# CV-module-schematics.net
KiCad netlist of a schematic drawn in EAGLE
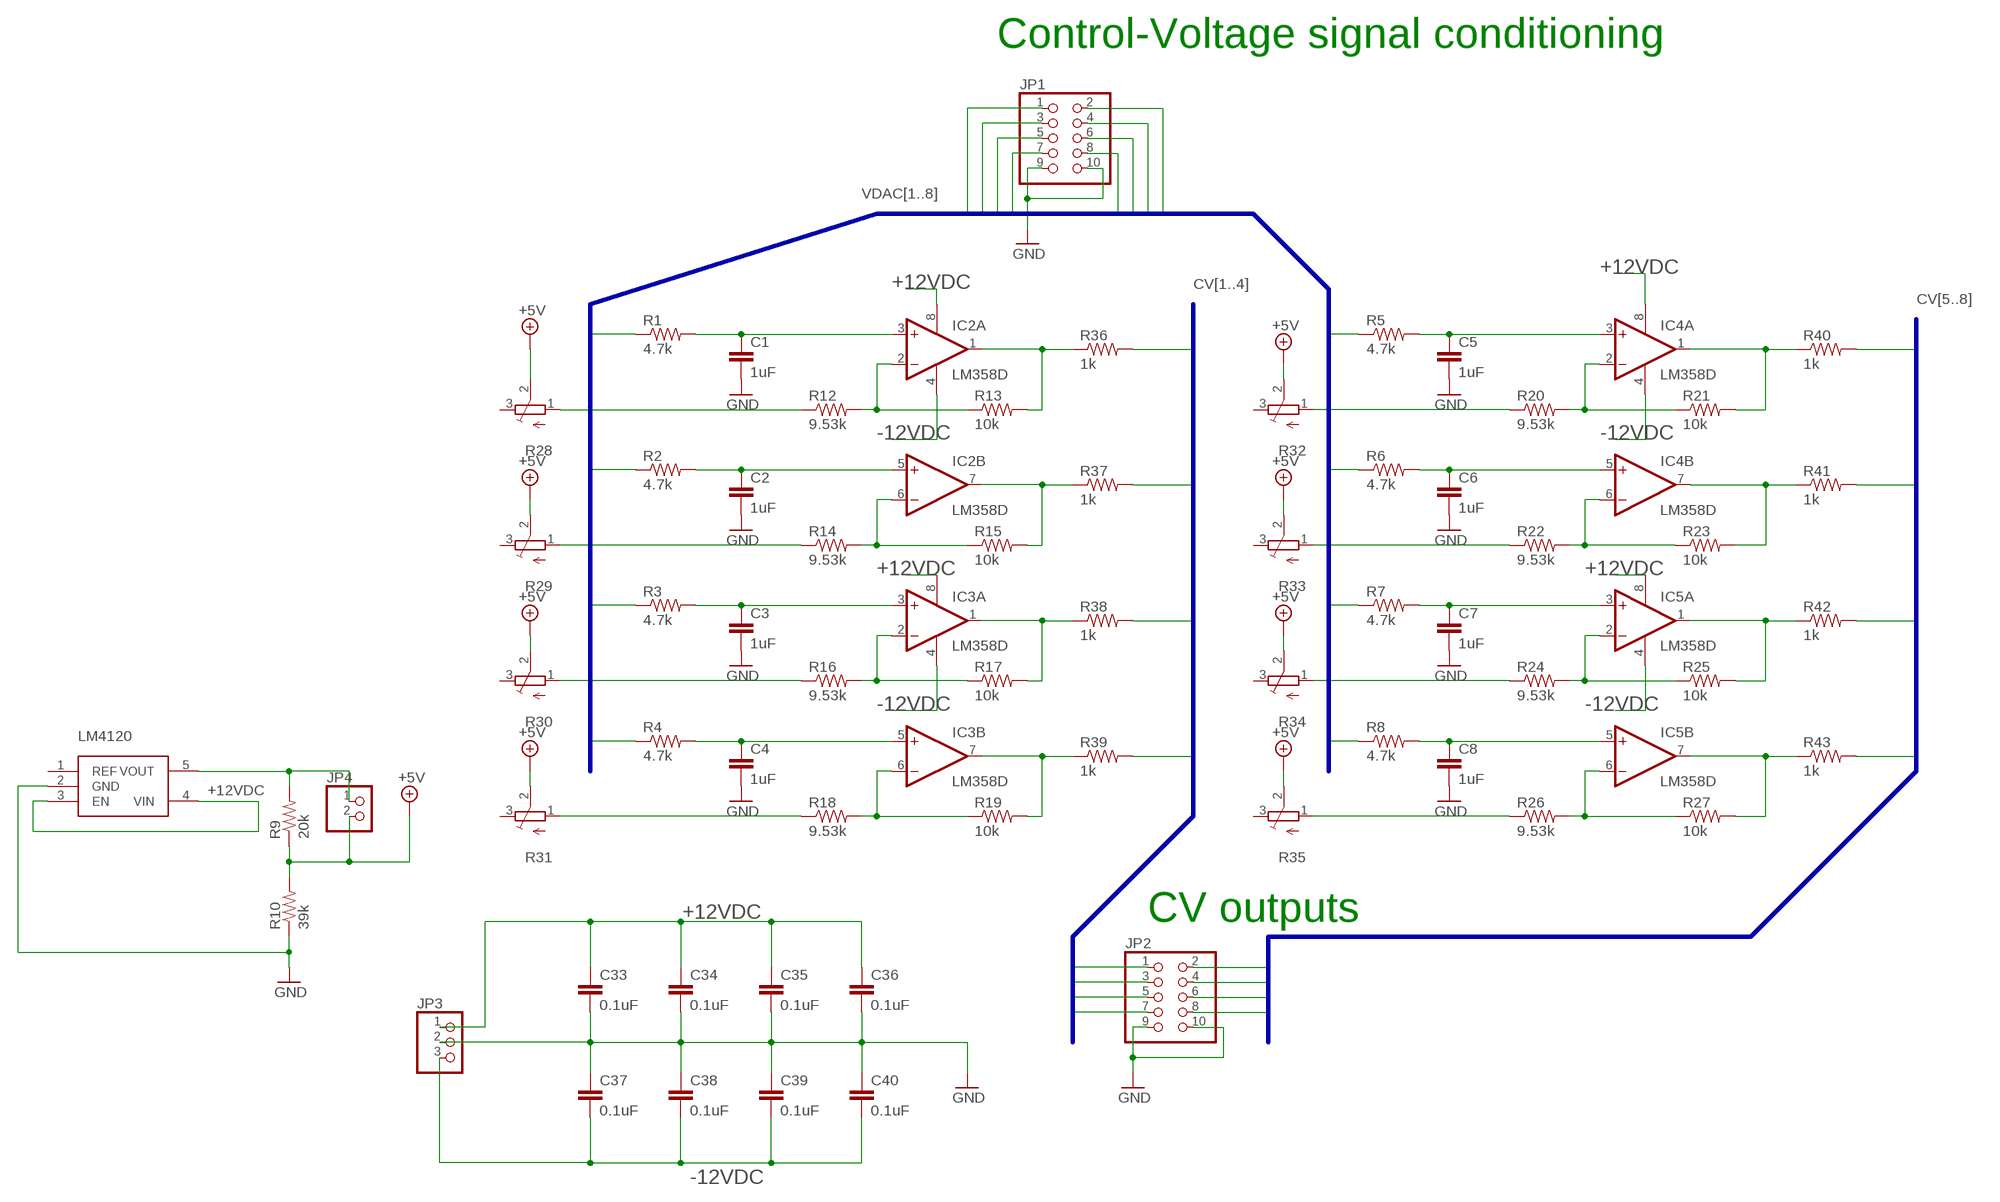
[diagram p0: schematic, sheet 1]

(export (version "E")
  (design (tool "Eeschema 10.0.6"))
  (components
    (comp (ref "C1")
      (value "1uF")
      (footprint "eagle-import:C0603")
      (libsource (lib "eagle-import") (part "C-EUC0603"))
    )
    (comp (ref "C2")
      (value "1uF")
      (footprint "eagle-import:C0603")
      (libsource (lib "eagle-import") (part "C-EUC0603"))
    )
    (comp (ref "C3")
      (value "1uF")
      (footprint "eagle-import:C0603")
      (libsource (lib "eagle-import") (part "C-EUC0603"))
    )
    (comp (ref "C4")
      (value "1uF")
      (footprint "eagle-import:C0603")
      (libsource (lib "eagle-import") (part "C-EUC0603"))
    )
    (comp (ref "C5")
      (value "1uF")
      (footprint "eagle-import:C0603")
      (libsource (lib "eagle-import") (part "C-EUC0603"))
    )
    (comp (ref "C6")
      (value "1uF")
      (footprint "eagle-import:C0603")
      (libsource (lib "eagle-import") (part "C-EUC0603"))
    )
    (comp (ref "C7")
      (value "1uF")
      (footprint "eagle-import:C0603")
      (libsource (lib "eagle-import") (part "C-EUC0603"))
    )
    (comp (ref "C8")
      (value "1uF")
      (footprint "eagle-import:C0603")
      (libsource (lib "eagle-import") (part "C-EUC0603"))
    )
    (comp (ref "C33")
      (value "0.1uF")
      (footprint "eagle-import:C0603")
      (libsource (lib "eagle-import") (part "C-EUC0603"))
    )
    (comp (ref "C34")
      (value "0.1uF")
      (footprint "eagle-import:C0603")
      (libsource (lib "eagle-import") (part "C-EUC0603"))
    )
    (comp (ref "C35")
      (value "0.1uF")
      (footprint "eagle-import:C0603")
      (libsource (lib "eagle-import") (part "C-EUC0603"))
    )
    (comp (ref "C36")
      (value "0.1uF")
      (footprint "eagle-import:C0603")
      (libsource (lib "eagle-import") (part "C-EUC0603"))
    )
    (comp (ref "C37")
      (value "0.1uF")
      (footprint "eagle-import:C0603")
      (libsource (lib "eagle-import") (part "C-EUC0603"))
    )
    (comp (ref "C38")
      (value "0.1uF")
      (footprint "eagle-import:C0603")
      (libsource (lib "eagle-import") (part "C-EUC0603"))
    )
    (comp (ref "C39")
      (value "0.1uF")
      (footprint "eagle-import:C0603")
      (libsource (lib "eagle-import") (part "C-EUC0603"))
    )
    (comp (ref "C40")
      (value "0.1uF")
      (footprint "eagle-import:C0603")
      (libsource (lib "eagle-import") (part "C-EUC0603"))
    )
    (comp (ref "IC2")
      (value "LM358D")
      (footprint "eagle-import:SO08")
      (libsource (lib "eagle-import") (part "LM358D"))
    )
    (comp (ref "IC3")
      (value "LM358D")
      (footprint "eagle-import:SO08")
      (libsource (lib "eagle-import") (part "LM358D"))
    )
    (comp (ref "IC4")
      (value "LM358D")
      (footprint "eagle-import:SO08")
      (libsource (lib "eagle-import") (part "LM358D"))
    )
    (comp (ref "IC5")
      (value "LM358D")
      (footprint "eagle-import:SO08")
      (libsource (lib "eagle-import") (part "LM358D"))
    )
    (comp (ref "JP1")
      (value "PINHD-2X5")
      (footprint "eagle-import:2X05")
      (libsource (lib "eagle-import") (part "PINHD-2X5"))
    )
    (comp (ref "JP2")
      (value "PINHD-2X5")
      (footprint "eagle-import:2X05")
      (libsource (lib "eagle-import") (part "PINHD-2X5"))
    )
    (comp (ref "JP3")
      (value "PINHD-1X3")
      (footprint "eagle-import:1X03")
      (libsource (lib "eagle-import") (part "PINHD-1X3"))
    )
    (comp (ref "JP4")
      (value "PINHD-1X2")
      (footprint "eagle-import:1X02")
      (libsource (lib "eagle-import") (part "PINHD-1X2"))
    )
    (comp (ref "LM4120")
      (value "LM4120")
      (footprint "eagle-import:SOT23-5")
      (libsource (lib "eagle-import") (part "LM4120"))
    )
    (comp (ref "R1")
      (value "4.7k")
      (footprint "eagle-import:R0603")
      (libsource (lib "eagle-import") (part "R-US_R0603"))
    )
    (comp (ref "R2")
      (value "4.7k")
      (footprint "eagle-import:R0603")
      (libsource (lib "eagle-import") (part "R-US_R0603"))
    )
    (comp (ref "R3")
      (value "4.7k")
      (footprint "eagle-import:R0603")
      (libsource (lib "eagle-import") (part "R-US_R0603"))
    )
    (comp (ref "R4")
      (value "4.7k")
      (footprint "eagle-import:R0603")
      (libsource (lib "eagle-import") (part "R-US_R0603"))
    )
    (comp (ref "R5")
      (value "4.7k")
      (footprint "eagle-import:R0603")
      (libsource (lib "eagle-import") (part "R-US_R0603"))
    )
    (comp (ref "R6")
      (value "4.7k")
      (footprint "eagle-import:R0603")
      (libsource (lib "eagle-import") (part "R-US_R0603"))
    )
    (comp (ref "R7")
      (value "4.7k")
      (footprint "eagle-import:R0603")
      (libsource (lib "eagle-import") (part "R-US_R0603"))
    )
    (comp (ref "R8")
      (value "4.7k")
      (footprint "eagle-import:R0603")
      (libsource (lib "eagle-import") (part "R-US_R0603"))
    )
    (comp (ref "R9")
      (value "20k")
      (footprint "eagle-import:R0603")
      (libsource (lib "eagle-import") (part "R-US_R0603"))
    )
    (comp (ref "R10")
      (value "39k")
      (footprint "eagle-import:R0603")
      (libsource (lib "eagle-import") (part "R-US_R0603"))
    )
    (comp (ref "R12")
      (value "9.53k")
      (footprint "eagle-import:R0603")
      (libsource (lib "eagle-import") (part "R-US_R0603"))
    )
    (comp (ref "R13")
      (value "10k")
      (footprint "eagle-import:R0603")
      (libsource (lib "eagle-import") (part "R-US_R0603"))
    )
    (comp (ref "R14")
      (value "9.53k")
      (footprint "eagle-import:R0603")
      (libsource (lib "eagle-import") (part "R-US_R0603"))
    )
    (comp (ref "R15")
      (value "10k")
      (footprint "eagle-import:R0603")
      (libsource (lib "eagle-import") (part "R-US_R0603"))
    )
    (comp (ref "R16")
      (value "9.53k")
      (footprint "eagle-import:R0603")
      (libsource (lib "eagle-import") (part "R-US_R0603"))
    )
    (comp (ref "R17")
      (value "10k")
      (footprint "eagle-import:R0603")
      (libsource (lib "eagle-import") (part "R-US_R0603"))
    )
    (comp (ref "R18")
      (value "9.53k")
      (footprint "eagle-import:R0603")
      (libsource (lib "eagle-import") (part "R-US_R0603"))
    )
    (comp (ref "R19")
      (value "10k")
      (footprint "eagle-import:R0603")
      (libsource (lib "eagle-import") (part "R-US_R0603"))
    )
    (comp (ref "R20")
      (value "9.53k")
      (footprint "eagle-import:R0603")
      (libsource (lib "eagle-import") (part "R-US_R0603"))
    )
    (comp (ref "R21")
      (value "10k")
      (footprint "eagle-import:R0603")
      (libsource (lib "eagle-import") (part "R-US_R0603"))
    )
    (comp (ref "R22")
      (value "9.53k")
      (footprint "eagle-import:R0603")
      (libsource (lib "eagle-import") (part "R-US_R0603"))
    )
    (comp (ref "R23")
      (value "10k")
      (footprint "eagle-import:R0603")
      (libsource (lib "eagle-import") (part "R-US_R0603"))
    )
    (comp (ref "R24")
      (value "9.53k")
      (footprint "eagle-import:R0603")
      (libsource (lib "eagle-import") (part "R-US_R0603"))
    )
    (comp (ref "R25")
      (value "10k")
      (footprint "eagle-import:R0603")
      (libsource (lib "eagle-import") (part "R-US_R0603"))
    )
    (comp (ref "R26")
      (value "9.53k")
      (footprint "eagle-import:R0603")
      (libsource (lib "eagle-import") (part "R-US_R0603"))
    )
    (comp (ref "R27")
      (value "10k")
      (footprint "eagle-import:R0603")
      (libsource (lib "eagle-import") (part "R-US_R0603"))
    )
    (comp (ref "R28")
      (value "TRIM_EU-3222W")
      (footprint "eagle-import:3222W")
      (libsource (lib "eagle-import") (part "TRIM_EU-3222W"))
    )
    (comp (ref "R29")
      (value "TRIM_EU-3222W")
      (footprint "eagle-import:3222W")
      (libsource (lib "eagle-import") (part "TRIM_EU-3222W"))
    )
    (comp (ref "R30")
      (value "TRIM_EU-3222W")
      (footprint "eagle-import:3222W")
      (libsource (lib "eagle-import") (part "TRIM_EU-3222W"))
    )
    (comp (ref "R31")
      (value "TRIM_EU-3222W")
      (footprint "eagle-import:3222W")
      (libsource (lib "eagle-import") (part "TRIM_EU-3222W"))
    )
    (comp (ref "R32")
      (value "TRIM_EU-3222W")
      (footprint "eagle-import:3222W")
      (libsource (lib "eagle-import") (part "TRIM_EU-3222W"))
    )
    (comp (ref "R33")
      (value "TRIM_EU-3222W")
      (footprint "eagle-import:3222W")
      (libsource (lib "eagle-import") (part "TRIM_EU-3222W"))
    )
    (comp (ref "R34")
      (value "TRIM_EU-3222W")
      (footprint "eagle-import:3222W")
      (libsource (lib "eagle-import") (part "TRIM_EU-3222W"))
    )
    (comp (ref "R35")
      (value "TRIM_EU-3222W")
      (footprint "eagle-import:3222W")
      (libsource (lib "eagle-import") (part "TRIM_EU-3222W"))
    )
    (comp (ref "R36")
      (value "1k")
      (footprint "eagle-import:R0603")
      (libsource (lib "eagle-import") (part "R-US_R0603"))
    )
    (comp (ref "R37")
      (value "1k")
      (footprint "eagle-import:R0603")
      (libsource (lib "eagle-import") (part "R-US_R0603"))
    )
    (comp (ref "R38")
      (value "1k")
      (footprint "eagle-import:R0603")
      (libsource (lib "eagle-import") (part "R-US_R0603"))
    )
    (comp (ref "R39")
      (value "1k")
      (footprint "eagle-import:R0603")
      (libsource (lib "eagle-import") (part "R-US_R0603"))
    )
    (comp (ref "R40")
      (value "1k")
      (footprint "eagle-import:R0603")
      (libsource (lib "eagle-import") (part "R-US_R0603"))
    )
    (comp (ref "R41")
      (value "1k")
      (footprint "eagle-import:R0603")
      (libsource (lib "eagle-import") (part "R-US_R0603"))
    )
    (comp (ref "R42")
      (value "1k")
      (footprint "eagle-import:R0603")
      (libsource (lib "eagle-import") (part "R-US_R0603"))
    )
    (comp (ref "R43")
      (value "1k")
      (footprint "eagle-import:R0603")
      (libsource (lib "eagle-import") (part "R-US_R0603"))
    )
  )
  (nets
    (net (code "1") (name "+5V") (class "Default")
      (node (ref "JP4") (pin "2") (pinfunction "2_2") (pintype "passive"))
      (node (ref "R10") (pin "2") (pinfunction "2_2") (pintype "passive"))
      (node (ref "R28") (pin "2") (pinfunction "S_2") (pintype "passive"))
      (node (ref "R29") (pin "2") (pinfunction "S_2") (pintype "passive"))
      (node (ref "R30") (pin "2") (pinfunction "S_2") (pintype "passive"))
      (node (ref "R31") (pin "2") (pinfunction "S_2") (pintype "passive"))
      (node (ref "R32") (pin "2") (pinfunction "S_2") (pintype "passive"))
      (node (ref "R33") (pin "2") (pinfunction "S_2") (pintype "passive"))
      (node (ref "R34") (pin "2") (pinfunction "S_2") (pintype "passive"))
      (node (ref "R35") (pin "2") (pinfunction "S_2") (pintype "passive"))
      (node (ref "R9") (pin "1") (pinfunction "1_1") (pintype "passive"))
    )
    (net (code "2") (name "/+12VDC") (class "Default")
      (node (ref "C33") (pin "1") (pinfunction "1_1") (pintype "passive"))
      (node (ref "C34") (pin "1") (pinfunction "1_1") (pintype "passive"))
      (node (ref "C35") (pin "1") (pinfunction "1_1") (pintype "passive"))
      (node (ref "C36") (pin "1") (pinfunction "1_1") (pintype "passive"))
      (node (ref "IC2") (pin "8") (pinfunction "V+_8") (pintype "power_in"))
      (node (ref "IC3") (pin "8") (pinfunction "V+_8") (pintype "power_in"))
      (node (ref "IC4") (pin "8") (pinfunction "V+_8") (pintype "power_in"))
      (node (ref "IC5") (pin "8") (pinfunction "V+_8") (pintype "power_in"))
      (node (ref "JP3") (pin "1") (pinfunction "1_1") (pintype "passive"))
      (node (ref "LM4120") (pin "3") (pinfunction "EN_3") (pintype "bidirectional"))
      (node (ref "LM4120") (pin "4") (pinfunction "VIN_4") (pintype "bidirectional"))
    )
    (net (code "3") (name "/-12VDC") (class "Default")
      (node (ref "C37") (pin "2") (pinfunction "2_2") (pintype "passive"))
      (node (ref "C38") (pin "2") (pinfunction "2_2") (pintype "passive"))
      (node (ref "C39") (pin "2") (pinfunction "2_2") (pintype "passive"))
      (node (ref "C40") (pin "2") (pinfunction "2_2") (pintype "passive"))
      (node (ref "IC2") (pin "4") (pinfunction "V-_4") (pintype "power_in"))
      (node (ref "IC3") (pin "4") (pinfunction "V-_4") (pintype "power_in"))
      (node (ref "IC4") (pin "4") (pinfunction "V-_4") (pintype "power_in"))
      (node (ref "IC5") (pin "4") (pinfunction "V-_4") (pintype "power_in"))
      (node (ref "JP3") (pin "3") (pinfunction "3_3") (pintype "passive"))
    )
    (net (code "4") (name "/CV1") (class "Default")
      (node (ref "JP2") (pin "1") (pinfunction "1_1") (pintype "passive"))
      (node (ref "R37") (pin "2") (pinfunction "2_2") (pintype "passive"))
    )
    (net (code "5") (name "/CV2") (class "Default")
      (node (ref "JP2") (pin "3") (pinfunction "3_3") (pintype "passive"))
      (node (ref "R36") (pin "2") (pinfunction "2_2") (pintype "passive"))
    )
    (net (code "6") (name "/CV3") (class "Default")
      (node (ref "JP2") (pin "5") (pinfunction "5_5") (pintype "passive"))
      (node (ref "R39") (pin "2") (pinfunction "2_2") (pintype "passive"))
    )
    (net (code "7") (name "/CV4") (class "Default")
      (node (ref "JP2") (pin "7") (pinfunction "7_7") (pintype "passive"))
      (node (ref "R38") (pin "2") (pinfunction "2_2") (pintype "passive"))
    )
    (net (code "8") (name "/CV5") (class "Default")
      (node (ref "JP2") (pin "2") (pinfunction "2_2") (pintype "passive"))
      (node (ref "R42") (pin "2") (pinfunction "2_2") (pintype "passive"))
    )
    (net (code "9") (name "/CV6") (class "Default")
      (node (ref "JP2") (pin "4") (pinfunction "4_4") (pintype "passive"))
      (node (ref "R43") (pin "2") (pinfunction "2_2") (pintype "passive"))
    )
    (net (code "10") (name "/CV7") (class "Default")
      (node (ref "JP2") (pin "6") (pinfunction "6_6") (pintype "passive"))
      (node (ref "R40") (pin "2") (pinfunction "2_2") (pintype "passive"))
    )
    (net (code "11") (name "/CV8") (class "Default")
      (node (ref "JP2") (pin "8") (pinfunction "8_8") (pintype "passive"))
      (node (ref "R41") (pin "2") (pinfunction "2_2") (pintype "passive"))
    )
    (net (code "14") (name "/VDAC1") (class "Default")
      (node (ref "JP1") (pin "1") (pinfunction "1_1") (pintype "passive"))
      (node (ref "R1") (pin "1") (pinfunction "1_1") (pintype "passive"))
    )
    (net (code "15") (name "/VDAC2") (class "Default")
      (node (ref "JP1") (pin "2") (pinfunction "2_2") (pintype "passive"))
      (node (ref "R2") (pin "1") (pinfunction "1_1") (pintype "passive"))
    )
    (net (code "16") (name "/VDAC3") (class "Default")
      (node (ref "JP1") (pin "3") (pinfunction "3_3") (pintype "passive"))
      (node (ref "R3") (pin "1") (pinfunction "1_1") (pintype "passive"))
    )
    (net (code "17") (name "/VDAC4") (class "Default")
      (node (ref "JP1") (pin "4") (pinfunction "4_4") (pintype "passive"))
      (node (ref "R4") (pin "1") (pinfunction "1_1") (pintype "passive"))
    )
    (net (code "18") (name "/VDAC5") (class "Default")
      (node (ref "JP1") (pin "5") (pinfunction "5_5") (pintype "passive"))
      (node (ref "R5") (pin "1") (pinfunction "1_1") (pintype "passive"))
    )
    (net (code "19") (name "/VDAC6") (class "Default")
      (node (ref "JP1") (pin "6") (pinfunction "6_6") (pintype "passive"))
      (node (ref "R6") (pin "1") (pinfunction "1_1") (pintype "passive"))
    )
    (net (code "20") (name "/VDAC7") (class "Default")
      (node (ref "JP1") (pin "7") (pinfunction "7_7") (pintype "passive"))
      (node (ref "R7") (pin "1") (pinfunction "1_1") (pintype "passive"))
    )
    (net (code "21") (name "/VDAC8") (class "Default")
      (node (ref "JP1") (pin "8") (pinfunction "8_8") (pintype "passive"))
      (node (ref "R8") (pin "1") (pinfunction "1_1") (pintype "passive"))
    )
    (net (code "23") (name "GND") (class "Default")
      (node (ref "C1") (pin "2") (pinfunction "2_2") (pintype "passive"))
      (node (ref "C2") (pin "2") (pinfunction "2_2") (pintype "passive"))
      (node (ref "C3") (pin "2") (pinfunction "2_2") (pintype "passive"))
      (node (ref "C33") (pin "2") (pinfunction "2_2") (pintype "passive"))
      (node (ref "C34") (pin "2") (pinfunction "2_2") (pintype "passive"))
      (node (ref "C35") (pin "2") (pinfunction "2_2") (pintype "passive"))
      (node (ref "C36") (pin "2") (pinfunction "2_2") (pintype "passive"))
      (node (ref "C37") (pin "1") (pinfunction "1_1") (pintype "passive"))
      (node (ref "C38") (pin "1") (pinfunction "1_1") (pintype "passive"))
      (node (ref "C39") (pin "1") (pinfunction "1_1") (pintype "passive"))
      (node (ref "C4") (pin "2") (pinfunction "2_2") (pintype "passive"))
      (node (ref "C40") (pin "1") (pinfunction "1_1") (pintype "passive"))
      (node (ref "C5") (pin "2") (pinfunction "2_2") (pintype "passive"))
      (node (ref "C6") (pin "2") (pinfunction "2_2") (pintype "passive"))
      (node (ref "C7") (pin "2") (pinfunction "2_2") (pintype "passive"))
      (node (ref "C8") (pin "2") (pinfunction "2_2") (pintype "passive"))
      (node (ref "JP1") (pin "10") (pinfunction "10_10") (pintype "passive"))
      (node (ref "JP1") (pin "9") (pinfunction "9_9") (pintype "passive"))
      (node (ref "JP2") (pin "10") (pinfunction "10_10") (pintype "passive"))
      (node (ref "JP2") (pin "9") (pinfunction "9_9") (pintype "passive"))
      (node (ref "JP3") (pin "2") (pinfunction "2_2") (pintype "passive"))
      (node (ref "LM4120") (pin "2") (pinfunction "GND_2") (pintype "bidirectional"))
      (node (ref "R10") (pin "1") (pinfunction "1_1") (pintype "passive"))
    )
    (net (code "24") (name "Net-(IC2A-+IN)") (class "Default")
      (node (ref "C1") (pin "1") (pinfunction "1_1") (pintype "passive"))
      (node (ref "IC2") (pin "3") (pinfunction "+IN_3") (pintype "input"))
      (node (ref "R1") (pin "2") (pinfunction "2_2") (pintype "passive"))
    )
    (net (code "25") (name "Net-(IC2A--IN)") (class "Default")
      (node (ref "IC2") (pin "2") (pinfunction "-IN_2") (pintype "input"))
      (node (ref "R12") (pin "2") (pinfunction "2_2") (pintype "passive"))
      (node (ref "R13") (pin "1") (pinfunction "1_1") (pintype "passive"))
    )
    (net (code "26") (name "Net-(IC2A-OUT)") (class "Default")
      (node (ref "IC2") (pin "1") (pinfunction "OUT_1") (pintype "output"))
      (node (ref "R13") (pin "2") (pinfunction "2_2") (pintype "passive"))
      (node (ref "R36") (pin "1") (pinfunction "1_1") (pintype "passive"))
    )
    (net (code "27") (name "Net-(IC2B-+IN)") (class "Default")
      (node (ref "C2") (pin "1") (pinfunction "1_1") (pintype "passive"))
      (node (ref "IC2") (pin "5") (pinfunction "+IN_5") (pintype "input"))
      (node (ref "R2") (pin "2") (pinfunction "2_2") (pintype "passive"))
    )
    (net (code "28") (name "Net-(IC2B--IN)") (class "Default")
      (node (ref "IC2") (pin "6") (pinfunction "-IN_6") (pintype "input"))
      (node (ref "R14") (pin "2") (pinfunction "2_2") (pintype "passive"))
      (node (ref "R15") (pin "1") (pinfunction "1_1") (pintype "passive"))
    )
    (net (code "29") (name "Net-(IC2B-OUT)") (class "Default")
      (node (ref "IC2") (pin "7") (pinfunction "OUT_7") (pintype "output"))
      (node (ref "R15") (pin "2") (pinfunction "2_2") (pintype "passive"))
      (node (ref "R37") (pin "1") (pinfunction "1_1") (pintype "passive"))
    )
    (net (code "30") (name "Net-(IC3A-+IN)") (class "Default")
      (node (ref "C3") (pin "1") (pinfunction "1_1") (pintype "passive"))
      (node (ref "IC3") (pin "3") (pinfunction "+IN_3") (pintype "input"))
      (node (ref "R3") (pin "2") (pinfunction "2_2") (pintype "passive"))
    )
    (net (code "31") (name "Net-(IC3A--IN)") (class "Default")
      (node (ref "IC3") (pin "2") (pinfunction "-IN_2") (pintype "input"))
      (node (ref "R16") (pin "2") (pinfunction "2_2") (pintype "passive"))
      (node (ref "R17") (pin "1") (pinfunction "1_1") (pintype "passive"))
    )
    (net (code "32") (name "Net-(IC3A-OUT)") (class "Default")
      (node (ref "IC3") (pin "1") (pinfunction "OUT_1") (pintype "output"))
      (node (ref "R17") (pin "2") (pinfunction "2_2") (pintype "passive"))
      (node (ref "R38") (pin "1") (pinfunction "1_1") (pintype "passive"))
    )
    (net (code "33") (name "Net-(IC3B-+IN)") (class "Default")
      (node (ref "C4") (pin "1") (pinfunction "1_1") (pintype "passive"))
      (node (ref "IC3") (pin "5") (pinfunction "+IN_5") (pintype "input"))
      (node (ref "R4") (pin "2") (pinfunction "2_2") (pintype "passive"))
    )
    (net (code "34") (name "Net-(IC3B--IN)") (class "Default")
      (node (ref "IC3") (pin "6") (pinfunction "-IN_6") (pintype "input"))
      (node (ref "R18") (pin "2") (pinfunction "2_2") (pintype "passive"))
      (node (ref "R19") (pin "1") (pinfunction "1_1") (pintype "passive"))
    )
    (net (code "35") (name "Net-(IC3B-OUT)") (class "Default")
      (node (ref "IC3") (pin "7") (pinfunction "OUT_7") (pintype "output"))
      (node (ref "R19") (pin "2") (pinfunction "2_2") (pintype "passive"))
      (node (ref "R39") (pin "1") (pinfunction "1_1") (pintype "passive"))
    )
    (net (code "36") (name "Net-(IC4A-+IN)") (class "Default")
      (node (ref "C5") (pin "1") (pinfunction "1_1") (pintype "passive"))
      (node (ref "IC4") (pin "3") (pinfunction "+IN_3") (pintype "input"))
      (node (ref "R5") (pin "2") (pinfunction "2_2") (pintype "passive"))
    )
    (net (code "37") (name "Net-(IC4A--IN)") (class "Default")
      (node (ref "IC4") (pin "2") (pinfunction "-IN_2") (pintype "input"))
      (node (ref "R20") (pin "2") (pinfunction "2_2") (pintype "passive"))
      (node (ref "R21") (pin "1") (pinfunction "1_1") (pintype "passive"))
    )
    (net (code "38") (name "Net-(IC4A-OUT)") (class "Default")
      (node (ref "IC4") (pin "1") (pinfunction "OUT_1") (pintype "output"))
      (node (ref "R21") (pin "2") (pinfunction "2_2") (pintype "passive"))
      (node (ref "R40") (pin "1") (pinfunction "1_1") (pintype "passive"))
    )
    (net (code "39") (name "Net-(IC4B-+IN)") (class "Default")
      (node (ref "C6") (pin "1") (pinfunction "1_1") (pintype "passive"))
      (node (ref "IC4") (pin "5") (pinfunction "+IN_5") (pintype "input"))
      (node (ref "R6") (pin "2") (pinfunction "2_2") (pintype "passive"))
    )
    (net (code "40") (name "Net-(IC4B--IN)") (class "Default")
      (node (ref "IC4") (pin "6") (pinfunction "-IN_6") (pintype "input"))
      (node (ref "R22") (pin "2") (pinfunction "2_2") (pintype "passive"))
      (node (ref "R23") (pin "1") (pinfunction "1_1") (pintype "passive"))
    )
    (net (code "41") (name "Net-(IC4B-OUT)") (class "Default")
      (node (ref "IC4") (pin "7") (pinfunction "OUT_7") (pintype "output"))
      (node (ref "R23") (pin "2") (pinfunction "2_2") (pintype "passive"))
      (node (ref "R41") (pin "1") (pinfunction "1_1") (pintype "passive"))
    )
    (net (code "42") (name "Net-(IC5A-+IN)") (class "Default")
      (node (ref "C7") (pin "1") (pinfunction "1_1") (pintype "passive"))
      (node (ref "IC5") (pin "3") (pinfunction "+IN_3") (pintype "input"))
      (node (ref "R7") (pin "2") (pinfunction "2_2") (pintype "passive"))
    )
    (net (code "43") (name "Net-(IC5A--IN)") (class "Default")
      (node (ref "IC5") (pin "2") (pinfunction "-IN_2") (pintype "input"))
      (node (ref "R24") (pin "2") (pinfunction "2_2") (pintype "passive"))
      (node (ref "R25") (pin "1") (pinfunction "1_1") (pintype "passive"))
    )
    (net (code "44") (name "Net-(IC5A-OUT)") (class "Default")
      (node (ref "IC5") (pin "1") (pinfunction "OUT_1") (pintype "output"))
      (node (ref "R25") (pin "2") (pinfunction "2_2") (pintype "passive"))
      (node (ref "R42") (pin "1") (pinfunction "1_1") (pintype "passive"))
    )
    (net (code "45") (name "Net-(IC5B-+IN)") (class "Default")
      (node (ref "C8") (pin "1") (pinfunction "1_1") (pintype "passive"))
      (node (ref "IC5") (pin "5") (pinfunction "+IN_5") (pintype "input"))
      (node (ref "R8") (pin "2") (pinfunction "2_2") (pintype "passive"))
    )
    (net (code "46") (name "Net-(IC5B--IN)") (class "Default")
      (node (ref "IC5") (pin "6") (pinfunction "-IN_6") (pintype "input"))
      (node (ref "R26") (pin "2") (pinfunction "2_2") (pintype "passive"))
      (node (ref "R27") (pin "1") (pinfunction "1_1") (pintype "passive"))
    )
    (net (code "47") (name "Net-(IC5B-OUT)") (class "Default")
      (node (ref "IC5") (pin "7") (pinfunction "OUT_7") (pintype "output"))
      (node (ref "R27") (pin "2") (pinfunction "2_2") (pintype "passive"))
      (node (ref "R43") (pin "1") (pinfunction "1_1") (pintype "passive"))
    )
    (net (code "48") (name "Net-(LM4120-VOUT)") (class "Default")
      (node (ref "JP4") (pin "1") (pinfunction "1_1") (pintype "passive"))
      (node (ref "LM4120") (pin "5") (pinfunction "VOUT_5") (pintype "bidirectional"))
      (node (ref "R9") (pin "2") (pinfunction "2_2") (pintype "passive"))
    )
    (net (code "49") (name "Net-(R28-A)") (class "Default")
      (node (ref "R12") (pin "1") (pinfunction "1_1") (pintype "passive"))
      (node (ref "R28") (pin "1") (pinfunction "A_1") (pintype "passive"))
    )
    (net (code "50") (name "Net-(R29-A)") (class "Default")
      (node (ref "R14") (pin "1") (pinfunction "1_1") (pintype "passive"))
      (node (ref "R29") (pin "1") (pinfunction "A_1") (pintype "passive"))
    )
    (net (code "51") (name "Net-(R30-A)") (class "Default")
      (node (ref "R16") (pin "1") (pinfunction "1_1") (pintype "passive"))
      (node (ref "R30") (pin "1") (pinfunction "A_1") (pintype "passive"))
    )
    (net (code "52") (name "Net-(R31-A)") (class "Default")
      (node (ref "R18") (pin "1") (pinfunction "1_1") (pintype "passive"))
      (node (ref "R31") (pin "1") (pinfunction "A_1") (pintype "passive"))
    )
    (net (code "53") (name "Net-(R32-A)") (class "Default")
      (node (ref "R20") (pin "1") (pinfunction "1_1") (pintype "passive"))
      (node (ref "R32") (pin "1") (pinfunction "A_1") (pintype "passive"))
    )
    (net (code "54") (name "Net-(R33-A)") (class "Default")
      (node (ref "R22") (pin "1") (pinfunction "1_1") (pintype "passive"))
      (node (ref "R33") (pin "1") (pinfunction "A_1") (pintype "passive"))
    )
    (net (code "55") (name "Net-(R34-A)") (class "Default")
      (node (ref "R24") (pin "1") (pinfunction "1_1") (pintype "passive"))
      (node (ref "R34") (pin "1") (pinfunction "A_1") (pintype "passive"))
    )
    (net (code "56") (name "Net-(R35-A)") (class "Default")
      (node (ref "R26") (pin "1") (pinfunction "1_1") (pintype "passive"))
      (node (ref "R35") (pin "1") (pinfunction "A_1") (pintype "passive"))
    )
    (net (code "57") (name "unconnected-(LM4120-REF-Pad1)") (class "Default")
      (node (ref "LM4120") (pin "1") (pinfunction "REF_1") (pintype "bidirectional"))
    )
    (net (code "58") (name "unconnected-(R28-E-Pad3)") (class "Default")
      (node (ref "R28") (pin "3") (pinfunction "E_3") (pintype "passive"))
    )
    (net (code "59") (name "unconnected-(R29-E-Pad3)") (class "Default")
      (node (ref "R29") (pin "3") (pinfunction "E_3") (pintype "passive"))
    )
    (net (code "60") (name "unconnected-(R30-E-Pad3)") (class "Default")
      (node (ref "R30") (pin "3") (pinfunction "E_3") (pintype "passive"))
    )
    (net (code "61") (name "unconnected-(R31-E-Pad3)") (class "Default")
      (node (ref "R31") (pin "3") (pinfunction "E_3") (pintype "passive"))
    )
    (net (code "62") (name "unconnected-(R32-E-Pad3)") (class "Default")
      (node (ref "R32") (pin "3") (pinfunction "E_3") (pintype "passive"))
    )
    (net (code "63") (name "unconnected-(R33-E-Pad3)") (class "Default")
      (node (ref "R33") (pin "3") (pinfunction "E_3") (pintype "passive"))
    )
    (net (code "64") (name "unconnected-(R34-E-Pad3)") (class "Default")
      (node (ref "R34") (pin "3") (pinfunction "E_3") (pintype "passive"))
    )
    (net (code "65") (name "unconnected-(R35-E-Pad3)") (class "Default")
      (node (ref "R35") (pin "3") (pinfunction "E_3") (pintype "passive"))
    )
  )
)
